# WifiLamp_Hardware.net
KiCad netlist of a schematic drawn in EAGLE
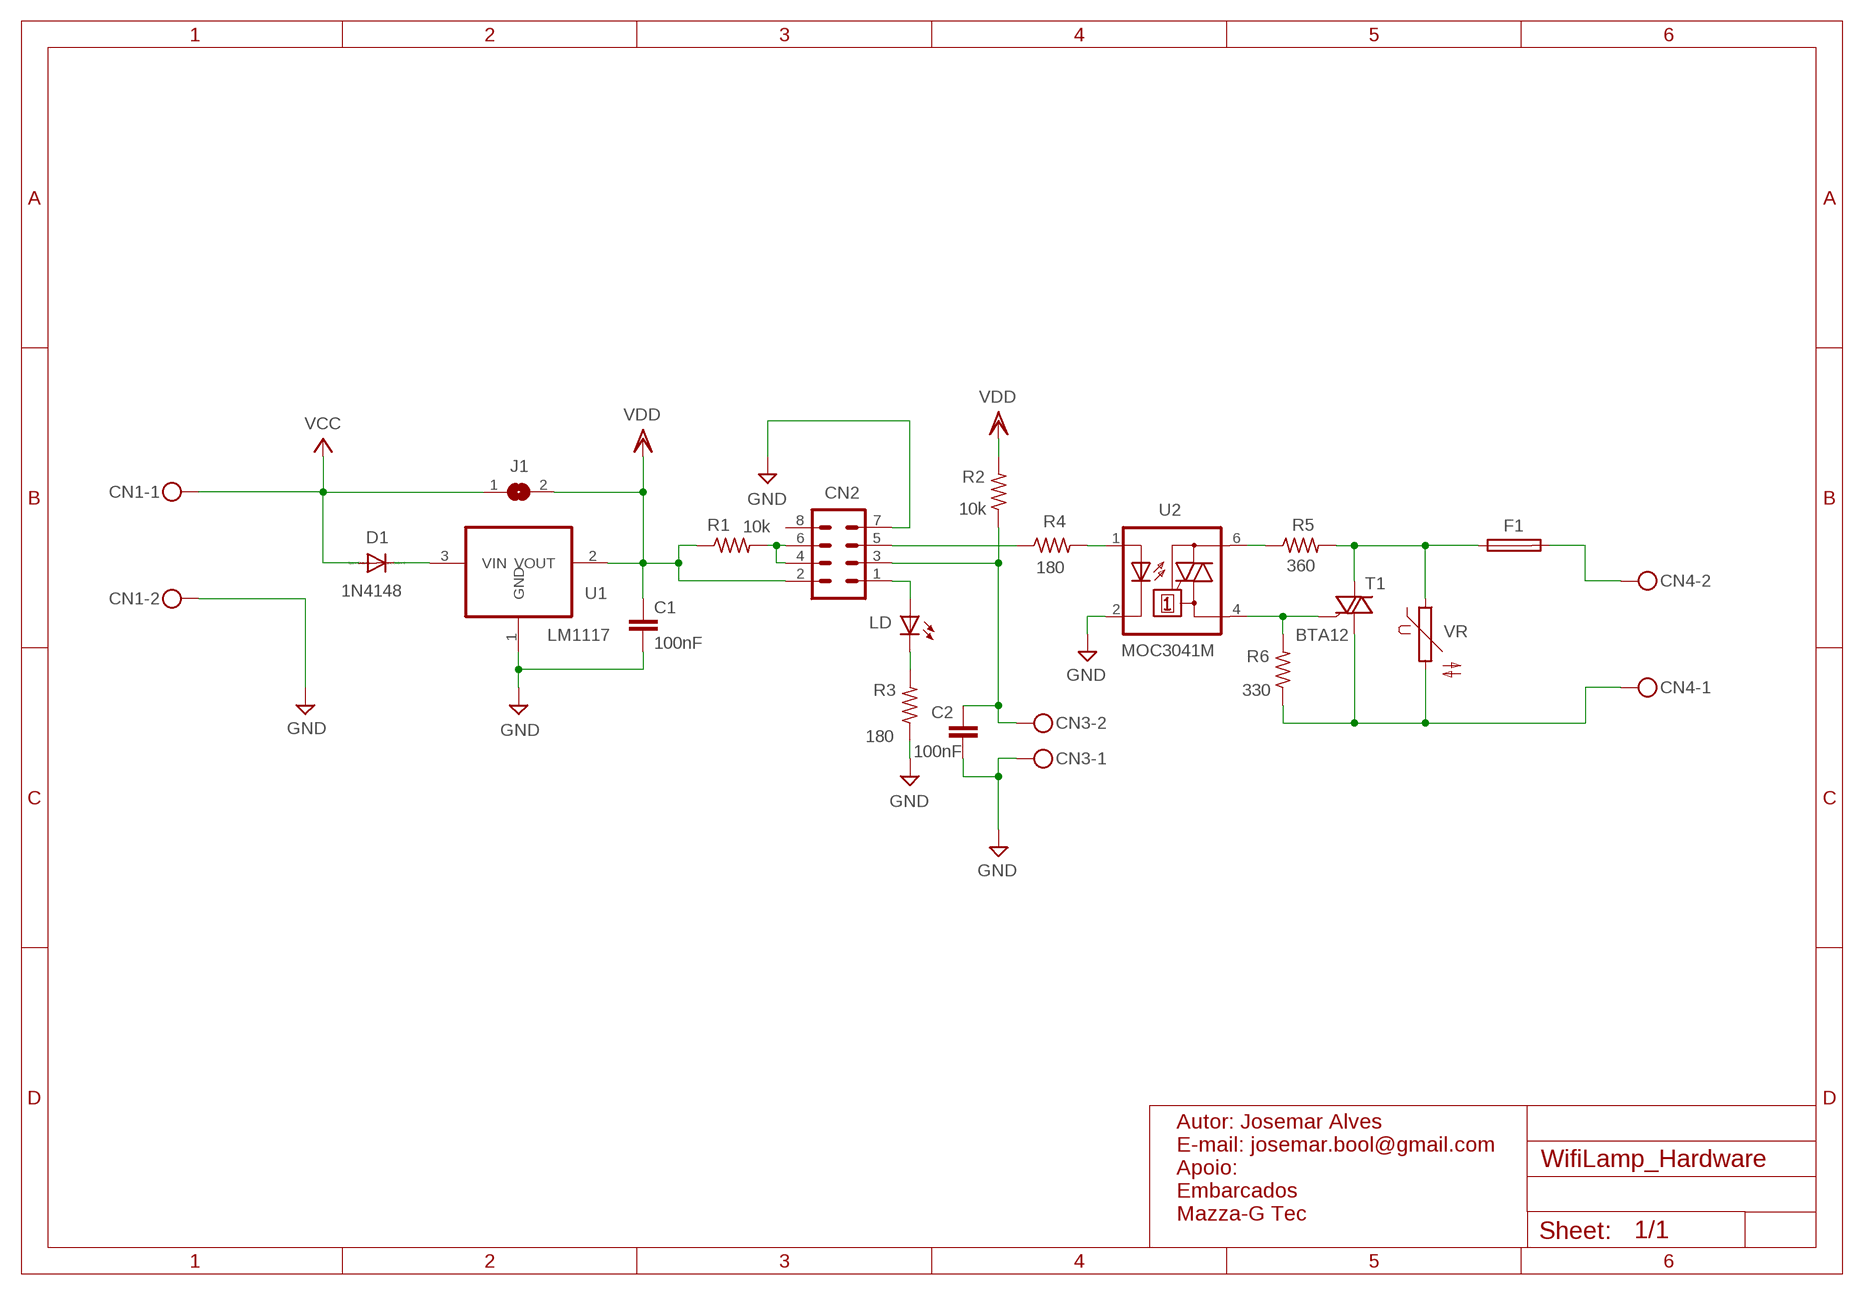
[diagram p0: schematic, sheet 1]

(export (version "E")
  (design (tool "Eeschema 10.0.6"))
  (components
    (comp (ref "C1")
      (value "100nF")
      (footprint "eagle-import:C0805K")
      (libsource (lib "eagle-import") (part "C-EUC0805K"))
    )
    (comp (ref "C2")
      (value "100nF")
      (footprint "eagle-import:C0805K")
      (libsource (lib "eagle-import") (part "C-EUC0805K"))
    )
    (comp (ref "CN1")
      (value "MKDSN1,5/2-5,08")
      (footprint "eagle-import:MKDSN1,5_2-5,08")
      (libsource (lib "eagle-import") (part "MKDSN1,5/2-5,08"))
    )
    (comp (ref "CN2")
      (value "MA04-2")
      (footprint "eagle-import:MA04-2")
      (libsource (lib "eagle-import") (part "MA04-2"))
    )
    (comp (ref "CN3")
      (value "MKDSN1,5/2-5,08")
      (footprint "eagle-import:MKDSN1,5_2-5,08")
      (libsource (lib "eagle-import") (part "MKDSN1,5/2-5,08"))
    )
    (comp (ref "CN4")
      (value "MKDSN1,5/2-5,08")
      (footprint "eagle-import:MKDSN1,5_2-5,08")
      (libsource (lib "eagle-import") (part "MKDSN1,5/2-5,08"))
    )
    (comp (ref "D1")
      (value "1N4148")
      (footprint "eagle-import:D-5")
      (libsource (lib "eagle-import") (part "DIODE-D-5"))
    )
    (comp (ref "F1")
      (value "FUSETR5")
      (footprint "eagle-import:TR5")
      (libsource (lib "eagle-import") (part "FUSETR5"))
    )
    (comp (ref "J1") (value "SJ") (footprint "eagle-import:SJ") (libsource (lib "eagle-import") (part "SJ")))
    (comp (ref "LD")
      (value "LED3MM")
      (footprint "eagle-import:LED3MM")
      (libsource (lib "eagle-import") (part "LED3MM"))
    )
    (comp (ref "R1")
      (value "10k")
      (footprint "eagle-import:0309V")
      (libsource (lib "eagle-import") (part "R-US_0309/V"))
    )
    (comp (ref "R2")
      (value "10k")
      (footprint "eagle-import:0309V")
      (libsource (lib "eagle-import") (part "R-US_0309/V"))
    )
    (comp (ref "R3")
      (value "180")
      (footprint "eagle-import:0207_10")
      (libsource (lib "eagle-import") (part "R-US_0207/10"))
    )
    (comp (ref "R4")
      (value "180")
      (footprint "eagle-import:0309V")
      (libsource (lib "eagle-import") (part "R-US_0309/V"))
    )
    (comp (ref "R5")
      (value "360")
      (footprint "eagle-import:0309V")
      (libsource (lib "eagle-import") (part "R-US_0309/V"))
    )
    (comp (ref "R6")
      (value "330")
      (footprint "eagle-import:0411V")
      (libsource (lib "eagle-import") (part "R-US_0411/3V"))
    )
    (comp (ref "T1")
      (value "BTA12")
      (footprint "eagle-import:TO220BV")
      (libsource (lib "eagle-import") (part "BT138-V"))
    )
    (comp (ref "U1")
      (value "LM1117")
      (footprint "eagle-import:SOT223")
      (fields (field (name "MPN") "REG1117"))
      (libsource (lib "eagle-import") (part "REG1117"))
    )
    (comp (ref "U2")
      (value "MOC3041M")
      (footprint "eagle-import:DIL06")
      (fields (field (name "MF") "FAIRCHILD SEMICONDUCTOR"))
      (libsource (lib "eagle-import") (part "MOC3041M"))
    )
    (comp (ref "VR")
      (value "S07K230")
      (footprint "eagle-import:S07K230")
      (libsource (lib "eagle-import") (part "S07K230"))
    )
  )
  (nets
    (net (code "1") (name "GND") (class "Default")
      (node (ref "C1") (pin "2") (pinfunction "2_2") (pintype "passive"))
      (node (ref "C2") (pin "2") (pinfunction "2_2") (pintype "passive"))
      (node (ref "CN1") (pin "2") (pinfunction "KL_2") (pintype "passive"))
      (node (ref "CN2") (pin "7") (pinfunction "7_7") (pintype "passive"))
      (node (ref "CN3") (pin "1") (pinfunction "KL_1") (pintype "passive"))
      (node (ref "R3") (pin "1") (pinfunction "1_1") (pintype "passive"))
      (node (ref "U1") (pin "1") (pinfunction "GND_1") (pintype "power_in"))
      (node (ref "U2") (pin "2") (pinfunction "C_2") (pintype "passive"))
    )
    (net (code "2") (name "Net-(CN2-Pad1)") (class "Default")
      (node (ref "CN2") (pin "1") (pinfunction "1_1") (pintype "passive"))
      (node (ref "LD") (pin "A") (pinfunction "A_A") (pintype "passive"))
    )
    (net (code "3") (name "Net-(CN2-Pad5)") (class "Default")
      (node (ref "CN2") (pin "5") (pinfunction "5_5") (pintype "passive"))
      (node (ref "R4") (pin "1") (pinfunction "1_1") (pintype "passive"))
    )
    (net (code "4") (name "Net-(CN2-Pad6)") (class "Default")
      (node (ref "CN2") (pin "6") (pinfunction "6_6") (pintype "passive"))
      (node (ref "R1") (pin "2") (pinfunction "2_2") (pintype "passive"))
    )
    (net (code "5") (name "Net-(CN3B-KL)") (class "Default")
      (node (ref "C2") (pin "1") (pinfunction "1_1") (pintype "passive"))
      (node (ref "CN2") (pin "3") (pinfunction "3_3") (pintype "passive"))
      (node (ref "CN3") (pin "2") (pinfunction "KL_2") (pintype "passive"))
      (node (ref "R2") (pin "1") (pinfunction "1_1") (pintype "passive"))
    )
    (net (code "6") (name "Net-(CN4A-KL)") (class "Default")
      (node (ref "CN4") (pin "1") (pinfunction "KL_1") (pintype "passive"))
      (node (ref "R6") (pin "1") (pinfunction "1_1") (pintype "passive"))
      (node (ref "T1") (pin "T1") (pinfunction "A1_T1") (pintype "passive"))
      (node (ref "VR") (pin "2") (pinfunction "2_2") (pintype "passive"))
    )
    (net (code "7") (name "Net-(CN4B-KL)") (class "Default")
      (node (ref "CN4") (pin "2") (pinfunction "KL_2") (pintype "passive"))
      (node (ref "F1") (pin "2") (pinfunction "2_2") (pintype "passive"))
    )
    (net (code "8") (name "Net-(LD-C)") (class "Default")
      (node (ref "LD") (pin "K") (pinfunction "C_K") (pintype "passive"))
      (node (ref "R3") (pin "2") (pinfunction "2_2") (pintype "passive"))
    )
    (net (code "9") (name "Net-(T1-A2)") (class "Default")
      (node (ref "F1") (pin "1") (pinfunction "1_1") (pintype "passive"))
      (node (ref "R5") (pin "2") (pinfunction "2_2") (pintype "passive"))
      (node (ref "T1") (pin "T2") (pinfunction "A2_T2") (pintype "passive"))
      (node (ref "VR") (pin "1") (pinfunction "1_1") (pintype "passive"))
    )
    (net (code "10") (name "Net-(U1-VIN)") (class "Default")
      (node (ref "D1") (pin "C") (pinfunction "C_C") (pintype "passive"))
      (node (ref "U1") (pin "3") (pinfunction "VIN_3") (pintype "input"))
    )
    (net (code "11") (name "Net-(U2-A)") (class "Default")
      (node (ref "R4") (pin "2") (pinfunction "2_2") (pintype "passive"))
      (node (ref "U2") (pin "1") (pinfunction "A_1") (pintype "passive"))
    )
    (net (code "12") (name "Net-(U2-A1)") (class "Default")
      (node (ref "R6") (pin "2") (pinfunction "2_2") (pintype "passive"))
      (node (ref "T1") (pin "G") (pinfunction "G_G") (pintype "passive"))
      (node (ref "U2") (pin "4") (pinfunction "A1_4") (pintype "passive"))
    )
    (net (code "13") (name "Net-(U2-A2)") (class "Default")
      (node (ref "R5") (pin "1") (pinfunction "1_1") (pintype "passive"))
      (node (ref "U2") (pin "6") (pinfunction "A2_6") (pintype "passive"))
    )
    (net (code "14") (name "VCC") (class "Default")
      (node (ref "CN1") (pin "1") (pinfunction "KL_1") (pintype "passive"))
      (node (ref "D1") (pin "A") (pinfunction "A_A") (pintype "passive"))
      (node (ref "J1") (pin "1") (pinfunction "1_1") (pintype "passive"))
    )
    (net (code "15") (name "VDD") (class "Default")
      (node (ref "C1") (pin "1") (pinfunction "1_1") (pintype "passive"))
      (node (ref "CN2") (pin "2") (pinfunction "2_2") (pintype "passive"))
      (node (ref "J1") (pin "2") (pinfunction "2_2") (pintype "passive"))
      (node (ref "R1") (pin "1") (pinfunction "1_1") (pintype "passive"))
      (node (ref "R2") (pin "2") (pinfunction "2_2") (pintype "passive"))
      (node (ref "U1") (pin "2") (pinfunction "VOUT_2") (pintype "output"))
    )
    (net (code "16") (name "unconnected-(CN2-Pad4)") (class "Default")
      (node (ref "CN2") (pin "4") (pinfunction "4_4") (pintype "passive"))
    )
    (net (code "17") (name "unconnected-(CN2-Pad8)") (class "Default")
      (node (ref "CN2") (pin "8") (pinfunction "8_8") (pintype "passive"))
    )
  )
)
